# 06-I225-1.net
KiCad netlist of a schematic drawn in Altium Designer
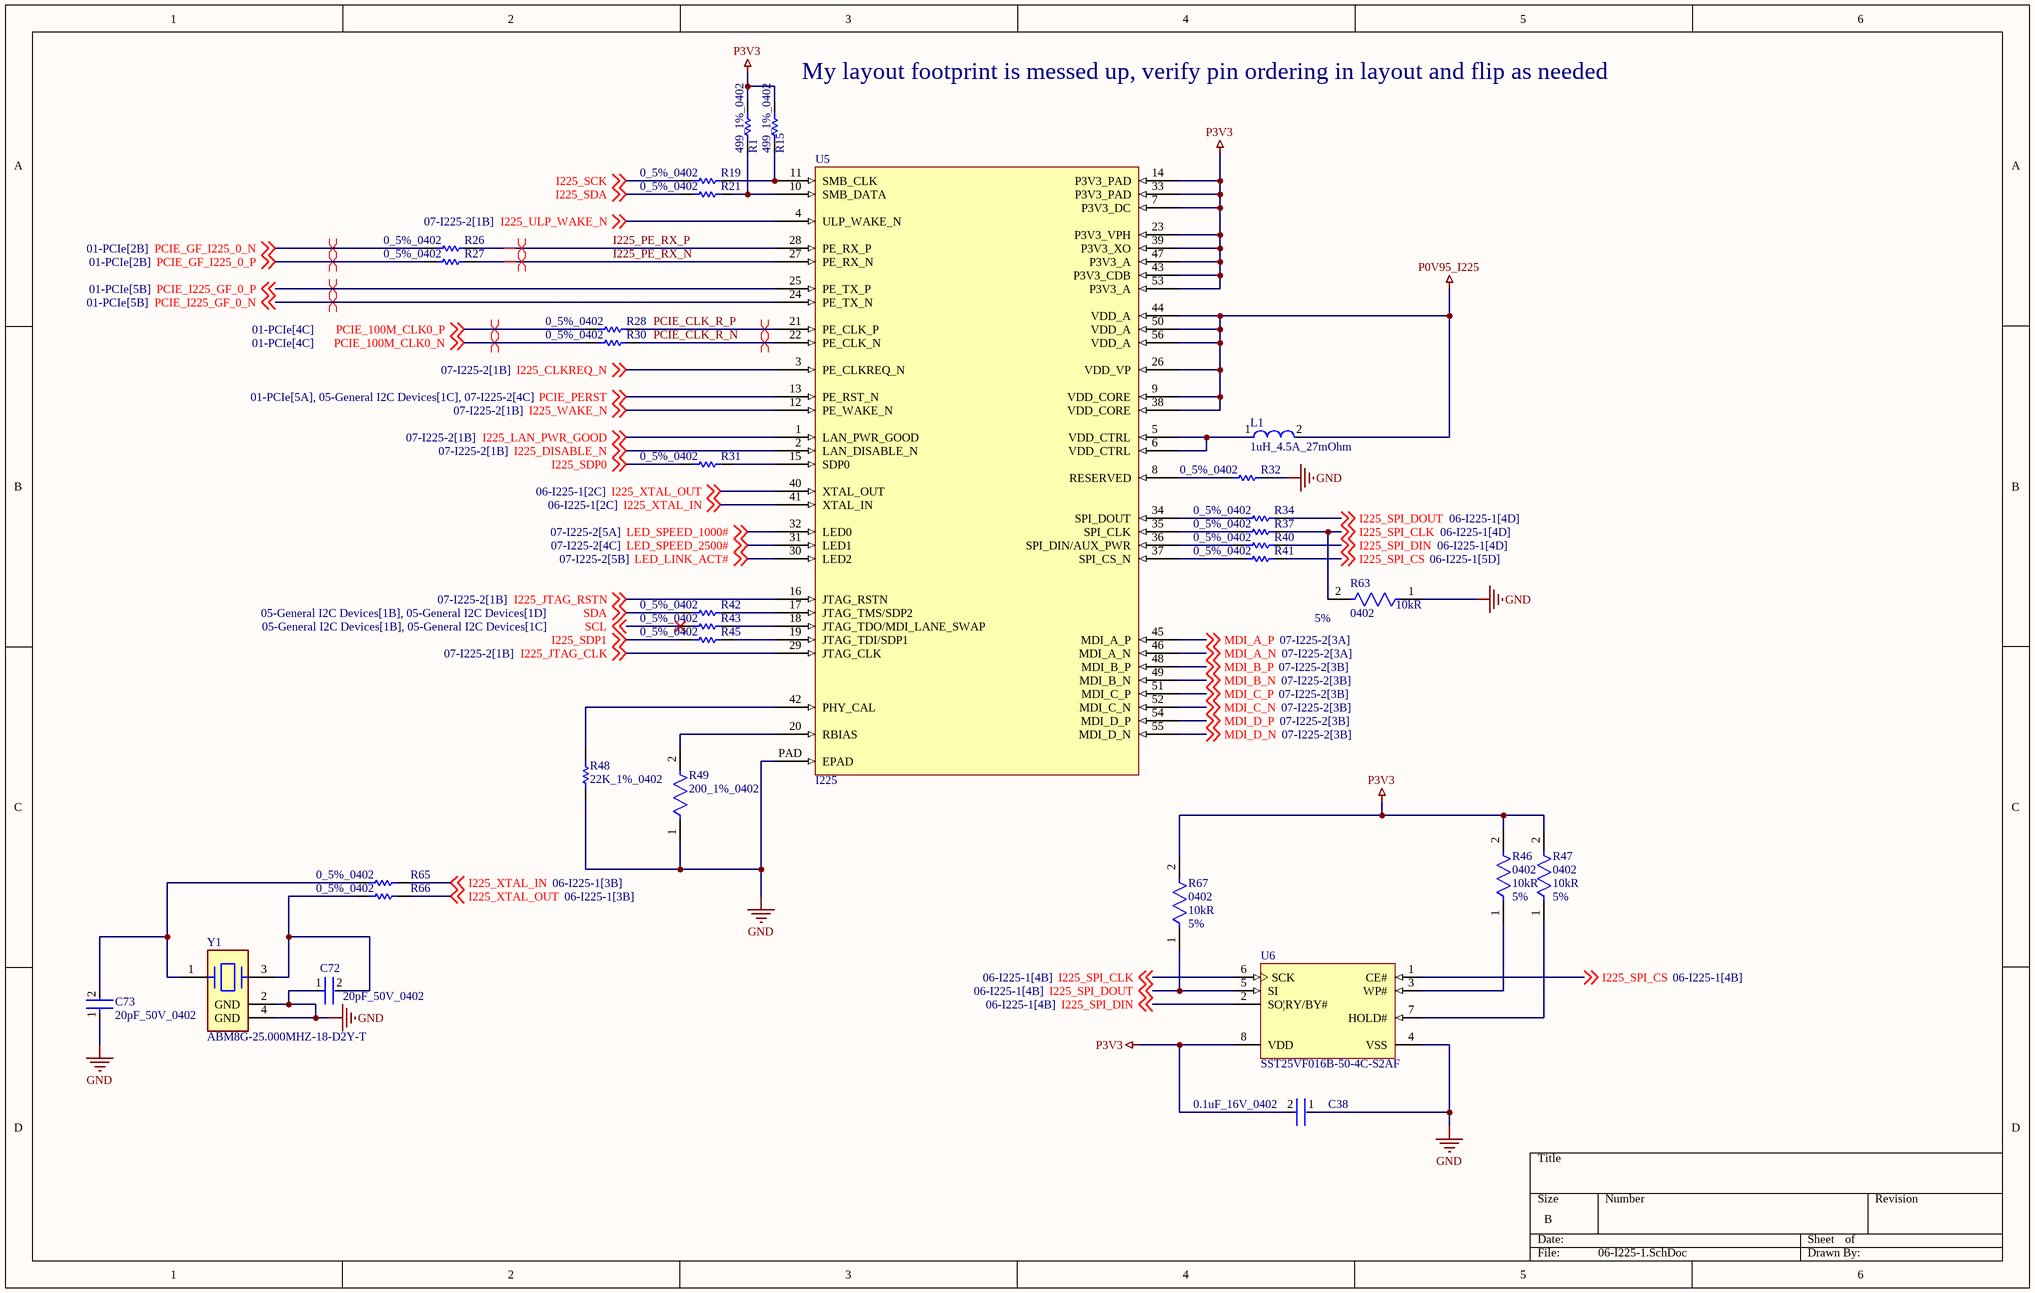
[diagram p0: 06-I225-1.SchDoc]

(export (version "E")
  (design (tool "Eeschema 10.0.6"))
  (components
    (comp (ref "C38")
      (value "0.1uF_16V_0402")
      (footprint "FP-GRM15-MFG")
      (description "CAP CER 0.1UF 16V X7R 0402")
      (fields (field (name "MANUFACTURER PART NUMBER") "GRM155R71C104KA88D") (field (name "TOLERANCE") "10%"))
      (libsource (lib "Altium Content Vault") (part "236180d848d6139a670b325ea6854c9"))
    )
    (comp (ref "C72")
      (value "20pF_50V_0402")
      (footprint "FP-C0402-BB-MFG")
      (description "CAP CER 20PF 50V 5% NP0 0402")
      (fields
        (field (name "MANUFACTURER PART NUMBER") "C0402C200J5GACTU")
        (field (name "OCTOPART") "https://octopart.com/c0402c200j5gactu-kemet-9143900")
      )
      (libsource (lib "Altium Content Vault") (part "b4654b650e69147ec39a6b967a45e02"))
    )
    (comp (ref "C73")
      (value "20pF_50V_0402")
      (footprint "FP-C0402-BB-MFG")
      (description "CAP CER 20PF 50V 5% NP0 0402")
      (fields
        (field (name "MANUFACTURER PART NUMBER") "C0402C200J5GACTU")
        (field (name "OCTOPART") "https://octopart.com/c0402c200j5gactu-kemet-9143900")
      )
      (libsource (lib "Altium Content Vault") (part "b4654b650e69147ec39a6b967a45e02"))
    )
    (comp (ref "L1")
      (value "1uH_4.5A_27mOhm")
      (footprint "FP-IHLP-1616BZ-FP_1_8545x-MFG")
      (description "Fixed Inductors Commercial Low DCR Series SMT 1uH 4.5A 27mΩ 20%")
      (fields (field (name "TOLERANCE") "20%"))
      (libsource (lib "Altium Content Vault") (part "725321dda6339637d4d059423bc1c3c"))
    )
    (comp (ref "R1")
      (value "499_1%_0402")
      (footprint "RESC1005X40X25LL05T05")
      (fields (field (name "MANUFACTURER") "Panasonic") (field (name "PART NUMBER") "ERJ-2RKF4990X"))
      (libsource (lib "Altium Content Vault") (part "RES"))
    )
    (comp (ref "R15")
      (value "499_1%_0402")
      (footprint "RESC1005X40X25LL05T05")
      (fields (field (name "MANUFACTURER") "Panasonic") (field (name "PART NUMBER") "ERJ-2RKF4990X"))
      (libsource (lib "Altium Content Vault") (part "RES"))
    )
    (comp (ref "R19")
      (value "0_5%_0402")
      (footprint "RESC1005X40X25LL10T10")
      (fields (field (name "MANUFACTURER") "KOA Speer") (field (name "PART NUMBER") "RK73Z1ETTP"))
      (libsource (lib "Altium Content Vault") (part "RES"))
    )
    (comp (ref "R21")
      (value "0_5%_0402")
      (footprint "RESC1005X40X25LL10T10")
      (fields (field (name "MANUFACTURER") "KOA Speer") (field (name "PART NUMBER") "RK73Z1ETTP"))
      (libsource (lib "Altium Content Vault") (part "RES"))
    )
    (comp (ref "R26")
      (value "0_5%_0402")
      (footprint "RESC1005X40X25LL10T10")
      (fields (field (name "MANUFACTURER") "KOA Speer") (field (name "PART NUMBER") "RK73Z1ETTP"))
      (libsource (lib "Altium Content Vault") (part "RES"))
    )
    (comp (ref "R27")
      (value "0_5%_0402")
      (footprint "RESC1005X40X25LL10T10")
      (fields (field (name "MANUFACTURER") "KOA Speer") (field (name "PART NUMBER") "RK73Z1ETTP"))
      (libsource (lib "Altium Content Vault") (part "RES"))
    )
    (comp (ref "R28")
      (value "0_5%_0402")
      (footprint "RESC1005X40X25LL10T10")
      (fields (field (name "MANUFACTURER") "KOA Speer") (field (name "PART NUMBER") "RK73Z1ETTP"))
      (libsource (lib "Altium Content Vault") (part "RES"))
    )
    (comp (ref "R30")
      (value "0_5%_0402")
      (footprint "RESC1005X40X25LL10T10")
      (fields (field (name "MANUFACTURER") "KOA Speer") (field (name "PART NUMBER") "RK73Z1ETTP"))
      (libsource (lib "Altium Content Vault") (part "RES"))
    )
    (comp (ref "R31")
      (value "0_5%_0402")
      (footprint "RESC1005X40X25LL10T10")
      (fields (field (name "MANUFACTURER") "KOA Speer") (field (name "PART NUMBER") "RK73Z1ETTP"))
      (libsource (lib "Altium Content Vault") (part "RES"))
    )
    (comp (ref "R32")
      (value "0_5%_0402")
      (footprint "RESC1005X40X25LL10T10")
      (fields (field (name "MANUFACTURER") "KOA Speer") (field (name "PART NUMBER") "RK73Z1ETTP"))
      (libsource (lib "Altium Content Vault") (part "RES"))
    )
    (comp (ref "R34")
      (value "0_5%_0402")
      (footprint "RESC1005X40X25LL10T10")
      (fields (field (name "MANUFACTURER") "KOA Speer") (field (name "PART NUMBER") "RK73Z1ETTP"))
      (libsource (lib "Altium Content Vault") (part "RES"))
    )
    (comp (ref "R37")
      (value "0_5%_0402")
      (footprint "RESC1005X40X25LL10T10")
      (fields (field (name "MANUFACTURER") "KOA Speer") (field (name "PART NUMBER") "RK73Z1ETTP"))
      (libsource (lib "Altium Content Vault") (part "RES"))
    )
    (comp (ref "R40")
      (value "0_5%_0402")
      (footprint "RESC1005X40X25LL10T10")
      (fields (field (name "MANUFACTURER") "KOA Speer") (field (name "PART NUMBER") "RK73Z1ETTP"))
      (libsource (lib "Altium Content Vault") (part "RES"))
    )
    (comp (ref "R41")
      (value "0_5%_0402")
      (footprint "RESC1005X40X25LL10T10")
      (fields (field (name "MANUFACTURER") "KOA Speer") (field (name "PART NUMBER") "RK73Z1ETTP"))
      (libsource (lib "Altium Content Vault") (part "RES"))
    )
    (comp (ref "R42")
      (value "0_5%_0402")
      (footprint "RESC1005X40X25LL10T10")
      (fields (field (name "MANUFACTURER") "KOA Speer") (field (name "PART NUMBER") "RK73Z1ETTP"))
      (libsource (lib "Altium Content Vault") (part "RES"))
    )
    (comp (ref "R43")
      (value "0_5%_0402")
      (footprint "RESC1005X40X25LL10T10")
      (fields (field (name "MANUFACTURER") "KOA Speer") (field (name "PART NUMBER") "RK73Z1ETTP"))
      (libsource (lib "Altium Content Vault") (part "RES"))
    )
    (comp (ref "R45")
      (value "0_5%_0402")
      (footprint "RESC1005X40X25LL10T10")
      (fields (field (name "MANUFACTURER") "KOA Speer") (field (name "PART NUMBER") "RK73Z1ETTP"))
      (libsource (lib "Altium Content Vault") (part "RES"))
    )
    (comp (ref "R46")
      (value "CRCW040210K0JNED")
      (footprint "FP-CRCW0402-e3-IPC_B")
      (description "RES Thick Film, 10kΩ, 5%, 0.063W, 200ppm/°C, 0402")
      (fields
        (field (name "CASE/PACKAGE") "0402")
        (field (name "RESISTANCE") "10kR")
        (field (name "TOLERANCE") "5%")
      )
      (libsource (lib "Altium Content Vault") (part "1029c3af85768c4190bb7ad29bc67b5"))
    )
    (comp (ref "R47")
      (value "CRCW040210K0JNED")
      (footprint "FP-CRCW0402-e3-IPC_B")
      (description "RES Thick Film, 10kΩ, 5%, 0.063W, 200ppm/°C, 0402")
      (fields
        (field (name "CASE/PACKAGE") "0402")
        (field (name "RESISTANCE") "10kR")
        (field (name "TOLERANCE") "5%")
      )
      (libsource (lib "Altium Content Vault") (part "1029c3af85768c4190bb7ad29bc67b5"))
    )
    (comp (ref "R48")
      (value "22K_1%_0402")
      (footprint "RESC1005X40X25NL05T05")
      (fields (field (name "PART NUMBER") "CRCW040222K0FKED") (field (name "MANUFACTURER") "Vishay Dale"))
      (libsource (lib "Altium Content Vault") (part "RES"))
    )
    (comp (ref "R49")
      (value "200_1%_0402")
      (footprint "FP-CRCW0402-e3-IPC_C")
      (description "RES Thick Film, 200Ω, 1%, 0.063W, 100ppm/°C, 0402")
      (fields (field (name "TOLERANCE") "1%"))
      (libsource (lib "Altium Content Vault") (part "1029c3af85768c4190bb7ad29bc67b5"))
    )
    (comp (ref "R63")
      (value "CRCW040210K0JNED")
      (footprint "FP-CRCW0402-e3-IPC_B")
      (description "RES Thick Film, 10kΩ, 5%, 0.063W, 200ppm/°C, 0402")
      (fields
        (field (name "CASE/PACKAGE") "0402")
        (field (name "RESISTANCE") "10kR")
        (field (name "TOLERANCE") "5%")
      )
      (libsource (lib "Altium Content Vault") (part "1029c3af85768c4190bb7ad29bc67b5"))
    )
    (comp (ref "R65")
      (value "0_5%_0402")
      (footprint "RESC1005X40X25LL10T10")
      (fields (field (name "MANUFACTURER") "KOA Speer") (field (name "PART NUMBER") "RK73Z1ETTP"))
      (libsource (lib "Altium Content Vault") (part "RES"))
    )
    (comp (ref "R66")
      (value "0_5%_0402")
      (footprint "RESC1005X40X25LL10T10")
      (fields (field (name "MANUFACTURER") "KOA Speer") (field (name "PART NUMBER") "RK73Z1ETTP"))
      (libsource (lib "Altium Content Vault") (part "RES"))
    )
    (comp (ref "R67")
      (value "CRCW040210K0JNED")
      (footprint "FP-CRCW0402-e3-IPC_B")
      (description "RES Thick Film, 10kΩ, 5%, 0.063W, 200ppm/°C, 0402")
      (fields
        (field (name "CASE/PACKAGE") "0402")
        (field (name "RESISTANCE") "10kR")
        (field (name "TOLERANCE") "5%")
      )
      (libsource (lib "Altium Content Vault") (part "1029c3af85768c4190bb7ad29bc67b5"))
    )
    (comp (ref "U5") (value "I225") (footprint "I225 QFN56") (libsource (lib "TimeStick_Lib") (part "I225")))
    (comp (ref "U6")
      (value "SST25VF016B-50-4C-S2AF")
      (footprint "MCHP-SOIC-S2A8_M")
      (description "16 Mbit SPI Serial Flash, 2.7 to 3.6 V, 50 MHz, 0 to 70 degC, 8-pin SOIC (S2A8), Tube")
      (fields (field (name "MANUFACTURER") "Microchip"))
      (libsource (lib "Altium Content Vault") (part "MCHP-SST25VFXXXB-SOIX-8"))
    )
    (comp (ref "Y1")
      (value "ABM8G-25.000MHZ-18-D2Y-T")
      (footprint "FP-ABM8G-MFG")
      (description "CRYSTAL 25.0000MHZ 18PF SMD")
      (fields
        (field (name "MANUFACTURER") "Abracon")
        (field (name "OCTOPART") "https://octopart.com/abm8g-25.000mhz-18-d2y-t-abracon-12676602")
      )
      (libsource (lib "Altium Content Vault") (part "82af6c543cb7a88a4cbd02a3a01c293"))
    )
  )
  (nets
    (net (code "1") (name "/I225_PE_RX_N") (class "Default")
      (node (ref "R27") (pin "2") (pinfunction "2_2") (pintype "passive"))
      (node (ref "U5") (pin "27") (pinfunction "PE_RX_N_27") (pintype "input"))
    )
    (net (code "2") (name "/I225_PE_RX_P") (class "Default")
      (node (ref "R26") (pin "2") (pinfunction "2_2") (pintype "passive"))
      (node (ref "U5") (pin "28") (pinfunction "PE_RX_P_28") (pintype "input"))
    )
    (net (code "3") (name "/PCIE_CLK_R_N") (class "Default")
      (node (ref "R30") (pin "2") (pinfunction "2_2") (pintype "passive"))
      (node (ref "U5") (pin "22") (pinfunction "PE_CLK_N_22") (pintype "input"))
    )
    (net (code "4") (name "/PCIE_CLK_R_P") (class "Default")
      (node (ref "R28") (pin "2") (pinfunction "2_2") (pintype "passive"))
      (node (ref "U5") (pin "21") (pinfunction "PE_CLK_P_21") (pintype "input"))
    )
    (net (code "5") (name "GND") (class "Default")
      (node (ref "C38") (pin "1") (pinfunction "1_1") (pintype "passive"))
      (node (ref "C72") (pin "1") (pinfunction "1_1") (pintype "passive"))
      (node (ref "C73") (pin "1") (pinfunction "1_1") (pintype "passive"))
      (node (ref "R32") (pin "2") (pinfunction "2_2") (pintype "passive"))
      (node (ref "R48") (pin "1") (pinfunction "1_1") (pintype "passive"))
      (node (ref "R49") (pin "1") (pinfunction "1_1") (pintype "passive"))
      (node (ref "R63") (pin "1") (pinfunction "1_1") (pintype "passive"))
      (node (ref "U5") (pin "PAD") (pinfunction "EPAD_PAD") (pintype "input"))
      (node (ref "U6") (pin "4") (pinfunction "VSS_4") (pintype "power_in"))
      (node (ref "Y1") (pin "2") (pinfunction "GND_2") (pintype "power_in"))
      (node (ref "Y1") (pin "4") (pinfunction "GND_4") (pintype "power_in"))
    )
    (net (code "6") (name "I225_CLKREQ_N") (class "Default")
      (node (ref "U5") (pin "3") (pinfunction "PE_CLKREQ_N_3") (pintype "input"))
    )
    (net (code "7") (name "I225_DISABLE_N") (class "Default")
      (node (ref "U5") (pin "2") (pinfunction "LAN_DISABLE_N_2") (pintype "input"))
    )
    (net (code "8") (name "I225_JTAG_CLK") (class "Default")
      (node (ref "U5") (pin "29") (pinfunction "JTAG_CLK_29") (pintype "input"))
    )
    (net (code "9") (name "I225_JTAG_RSTN") (class "Default")
      (node (ref "U5") (pin "16") (pinfunction "JTAG_RSTN_16") (pintype "input"))
    )
    (net (code "10") (name "I225_LAN_PWR_GOOD") (class "Default")
      (node (ref "U5") (pin "1") (pinfunction "LAN_PWR_GOOD_1") (pintype "input"))
    )
    (net (code "11") (name "I225_SCK") (class "Default")
      (node (ref "R19") (pin "1") (pinfunction "1_1") (pintype "passive"))
    )
    (net (code "12") (name "I225_SDA") (class "Default")
      (node (ref "R21") (pin "1") (pinfunction "1_1") (pintype "passive"))
    )
    (net (code "13") (name "I225_SDP0") (class "Default")
      (node (ref "R31") (pin "1") (pinfunction "1_1") (pintype "passive"))
    )
    (net (code "14") (name "I225_SDP1") (class "Default")
      (node (ref "R45") (pin "1") (pinfunction "1_1") (pintype "passive"))
    )
    (net (code "15") (name "I225_SPI_CLK") (class "Default")
      (node (ref "R37") (pin "2") (pinfunction "2_2") (pintype "passive"))
      (node (ref "R63") (pin "2") (pinfunction "2_2") (pintype "passive"))
      (node (ref "U6") (pin "6") (pinfunction "SCK_6") (pintype "input"))
    )
    (net (code "16") (name "I225_SPI_CS") (class "Default")
      (node (ref "R41") (pin "2") (pinfunction "2_2") (pintype "passive"))
      (node (ref "U6") (pin "1") (pinfunction "CE#_1") (pintype "input"))
    )
    (net (code "17") (name "I225_SPI_DIN") (class "Default")
      (node (ref "R40") (pin "2") (pinfunction "2_2") (pintype "passive"))
      (node (ref "U6") (pin "2") (pinfunction "SO¦RY/BY#_2") (pintype "tri_state"))
    )
    (net (code "18") (name "I225_SPI_DOUT") (class "Default")
      (node (ref "R34") (pin "2") (pinfunction "2_2") (pintype "passive"))
      (node (ref "R67") (pin "1") (pinfunction "1_1") (pintype "passive"))
      (node (ref "U6") (pin "5") (pinfunction "SI_5") (pintype "input"))
    )
    (net (code "19") (name "I225_ULP_WAKE_N") (class "Default")
      (node (ref "U5") (pin "4") (pinfunction "ULP_WAKE_N_4") (pintype "input"))
    )
    (net (code "20") (name "I225_WAKE_N") (class "Default")
      (node (ref "U5") (pin "12") (pinfunction "PE_WAKE_N_12") (pintype "input"))
    )
    (net (code "21") (name "I225_XTAL_IN") (class "Default")
      (node (ref "R65") (pin "2") (pinfunction "2_2") (pintype "passive"))
      (node (ref "U5") (pin "41") (pinfunction "XTAL_IN_41") (pintype "input"))
    )
    (net (code "22") (name "I225_XTAL_OUT") (class "Default")
      (node (ref "R66") (pin "2") (pinfunction "2_2") (pintype "passive"))
      (node (ref "U5") (pin "40") (pinfunction "XTAL_OUT_40") (pintype "input"))
    )
    (net (code "23") (name "LED_LINK_ACT#") (class "Default")
      (node (ref "U5") (pin "30") (pinfunction "LED2_30") (pintype "input"))
    )
    (net (code "24") (name "LED_SPEED_1000#") (class "Default")
      (node (ref "U5") (pin "32") (pinfunction "LED0_32") (pintype "input"))
    )
    (net (code "25") (name "LED_SPEED_2500#") (class "Default")
      (node (ref "U5") (pin "31") (pinfunction "LED1_31") (pintype "input"))
    )
    (net (code "26") (name "MDI_A_N") (class "Default")
      (node (ref "U5") (pin "46") (pinfunction "MDI_A_N_46") (pintype "input"))
    )
    (net (code "27") (name "MDI_A_P") (class "Default")
      (node (ref "U5") (pin "45") (pinfunction "MDI_A_P_45") (pintype "input"))
    )
    (net (code "28") (name "MDI_B_N") (class "Default")
      (node (ref "U5") (pin "49") (pinfunction "MDI_B_N_49") (pintype "input"))
    )
    (net (code "29") (name "MDI_B_P") (class "Default")
      (node (ref "U5") (pin "48") (pinfunction "MDI_B_P_48") (pintype "input"))
    )
    (net (code "30") (name "MDI_C_N") (class "Default")
      (node (ref "U5") (pin "52") (pinfunction "MDI_C_N_52") (pintype "input"))
    )
    (net (code "31") (name "MDI_C_P") (class "Default")
      (node (ref "U5") (pin "51") (pinfunction "MDI_C_P_51") (pintype "input"))
    )
    (net (code "32") (name "MDI_D_N") (class "Default")
      (node (ref "U5") (pin "55") (pinfunction "MDI_D_N_55") (pintype "input"))
    )
    (net (code "33") (name "MDI_D_P") (class "Default")
      (node (ref "U5") (pin "54") (pinfunction "MDI_D_P_54") (pintype "input"))
    )
    (net (code "34") (name "Net-(C72-Pad2)") (class "Default")
      (node (ref "C72") (pin "2") (pinfunction "2_2") (pintype "passive"))
      (node (ref "R66") (pin "1") (pinfunction "1_1") (pintype "passive"))
      (node (ref "Y1") (pin "3") (pinfunction "3_3") (pintype "passive"))
    )
    (net (code "35") (name "Net-(C73-Pad2)") (class "Default")
      (node (ref "C73") (pin "2") (pinfunction "2_2") (pintype "passive"))
      (node (ref "R65") (pin "1") (pinfunction "1_1") (pintype "passive"))
      (node (ref "Y1") (pin "1") (pinfunction "1_1") (pintype "passive"))
    )
    (net (code "36") (name "Net-(L1-Pad1)") (class "Default")
      (node (ref "L1") (pin "1") (pinfunction "1_1") (pintype "passive"))
      (node (ref "U5") (pin "5") (pinfunction "VDD_CTRL_5") (pintype "input"))
      (node (ref "U5") (pin "6") (pinfunction "VDD_CTRL_6") (pintype "input"))
    )
    (net (code "37") (name "Net-(U5-JTAG_TDI{slash}SDP1)") (class "Default")
      (node (ref "R45") (pin "2") (pinfunction "2_2") (pintype "passive"))
      (node (ref "U5") (pin "19") (pinfunction "JTAG_TDI/SDP1_19") (pintype "input"))
    )
    (net (code "38") (name "Net-(U5-JTAG_TDO{slash}MDI_LANE_SWAP)") (class "Default")
      (node (ref "R43") (pin "2") (pinfunction "2_2") (pintype "passive"))
      (node (ref "U5") (pin "18") (pinfunction "JTAG_TDO/MDI_LANE_SWAP_18") (pintype "input"))
    )
    (net (code "39") (name "Net-(U5-JTAG_TMS{slash}SDP2)") (class "Default")
      (node (ref "R42") (pin "2") (pinfunction "2_2") (pintype "passive"))
      (node (ref "U5") (pin "17") (pinfunction "JTAG_TMS/SDP2_17") (pintype "input"))
    )
    (net (code "40") (name "Net-(U5-PHY_CAL)") (class "Default")
      (node (ref "R48") (pin "2") (pinfunction "2_2") (pintype "passive"))
      (node (ref "U5") (pin "42") (pinfunction "PHY_CAL_42") (pintype "input"))
    )
    (net (code "41") (name "Net-(U5-RBIAS)") (class "Default")
      (node (ref "R49") (pin "2") (pinfunction "2_2") (pintype "passive"))
      (node (ref "U5") (pin "20") (pinfunction "RBIAS_20") (pintype "input"))
    )
    (net (code "42") (name "Net-(U5-RESERVED)") (class "Default")
      (node (ref "R32") (pin "1") (pinfunction "1_1") (pintype "passive"))
      (node (ref "U5") (pin "8") (pinfunction "RESERVED_8") (pintype "input"))
    )
    (net (code "43") (name "Net-(U5-SDP0)") (class "Default")
      (node (ref "R31") (pin "2") (pinfunction "2_2") (pintype "passive"))
      (node (ref "U5") (pin "15") (pinfunction "SDP0_15") (pintype "input"))
    )
    (net (code "44") (name "Net-(U5-SMB_CLK)") (class "Default")
      (node (ref "R15") (pin "1") (pinfunction "1_1") (pintype "passive"))
      (node (ref "R19") (pin "2") (pinfunction "2_2") (pintype "passive"))
      (node (ref "U5") (pin "11") (pinfunction "SMB_CLK_11") (pintype "input"))
    )
    (net (code "45") (name "Net-(U5-SMB_DATA)") (class "Default")
      (node (ref "R1") (pin "1") (pinfunction "1_1") (pintype "passive"))
      (node (ref "R21") (pin "2") (pinfunction "2_2") (pintype "passive"))
      (node (ref "U5") (pin "10") (pinfunction "SMB_DATA_10") (pintype "input"))
    )
    (net (code "46") (name "Net-(U5-SPI_CLK)") (class "Default")
      (node (ref "R37") (pin "1") (pinfunction "1_1") (pintype "passive"))
      (node (ref "U5") (pin "35") (pinfunction "SPI_CLK_35") (pintype "input"))
    )
    (net (code "47") (name "Net-(U5-SPI_CS_N)") (class "Default")
      (node (ref "R41") (pin "1") (pinfunction "1_1") (pintype "passive"))
      (node (ref "U5") (pin "37") (pinfunction "SPI_CS_N_37") (pintype "input"))
    )
    (net (code "48") (name "Net-(U5-SPI_DIN{slash}AUX_PWR)") (class "Default")
      (node (ref "R40") (pin "1") (pinfunction "1_1") (pintype "passive"))
      (node (ref "U5") (pin "36") (pinfunction "SPI_DIN/AUX_PWR_36") (pintype "input"))
    )
    (net (code "49") (name "Net-(U5-SPI_DOUT)") (class "Default")
      (node (ref "R34") (pin "1") (pinfunction "1_1") (pintype "passive"))
      (node (ref "U5") (pin "34") (pinfunction "SPI_DOUT_34") (pintype "input"))
    )
    (net (code "50") (name "Net-(U6-HOLD#)") (class "Default")
      (node (ref "R47") (pin "1") (pinfunction "1_1") (pintype "passive"))
      (node (ref "U6") (pin "7") (pinfunction "HOLD#_7") (pintype "input"))
    )
    (net (code "51") (name "Net-(U6-WP#)") (class "Default")
      (node (ref "R46") (pin "1") (pinfunction "1_1") (pintype "passive"))
      (node (ref "U6") (pin "3") (pinfunction "WP#_3") (pintype "input"))
    )
    (net (code "52") (name "P0V95_I225") (class "Default")
      (node (ref "L1") (pin "2") (pinfunction "2_2") (pintype "passive"))
      (node (ref "U5") (pin "26") (pinfunction "VDD_VP_26") (pintype "input"))
      (node (ref "U5") (pin "38") (pinfunction "VDD_CORE_38") (pintype "input"))
      (node (ref "U5") (pin "44") (pinfunction "VDD_A_44") (pintype "input"))
      (node (ref "U5") (pin "50") (pinfunction "VDD_A_50") (pintype "input"))
      (node (ref "U5") (pin "56") (pinfunction "VDD_A_56") (pintype "input"))
      (node (ref "U5") (pin "9") (pinfunction "VDD_CORE_9") (pintype "input"))
    )
    (net (code "53") (name "P3V3") (class "Default")
      (node (ref "C38") (pin "2") (pinfunction "2_2") (pintype "passive"))
      (node (ref "R1") (pin "2") (pinfunction "2_2") (pintype "passive"))
      (node (ref "R15") (pin "2") (pinfunction "2_2") (pintype "passive"))
      (node (ref "R46") (pin "2") (pinfunction "2_2") (pintype "passive"))
      (node (ref "R47") (pin "2") (pinfunction "2_2") (pintype "passive"))
      (node (ref "R67") (pin "2") (pinfunction "2_2") (pintype "passive"))
      (node (ref "U5") (pin "14") (pinfunction "P3V3_PAD_14") (pintype "input"))
      (node (ref "U5") (pin "23") (pinfunction "P3V3_VPH_23") (pintype "input"))
      (node (ref "U5") (pin "33") (pinfunction "P3V3_PAD_33") (pintype "input"))
      (node (ref "U5") (pin "39") (pinfunction "P3V3_XO_39") (pintype "input"))
      (node (ref "U5") (pin "43") (pinfunction "P3V3_CDB_43") (pintype "input"))
      (node (ref "U5") (pin "47") (pinfunction "P3V3_A_47") (pintype "input"))
      (node (ref "U5") (pin "53") (pinfunction "P3V3_A_53") (pintype "input"))
      (node (ref "U5") (pin "7") (pinfunction "P3V3_DC_7") (pintype "input"))
      (node (ref "U6") (pin "8") (pinfunction "VDD_8") (pintype "power_in"))
    )
    (net (code "54") (name "PCIE_100M_CLK0_N") (class "Default")
      (node (ref "R30") (pin "1") (pinfunction "1_1") (pintype "passive"))
    )
    (net (code "55") (name "PCIE_100M_CLK0_P") (class "Default")
      (node (ref "R28") (pin "1") (pinfunction "1_1") (pintype "passive"))
    )
    (net (code "56") (name "PCIE_GF_I225_0_N") (class "Default")
      (node (ref "R26") (pin "1") (pinfunction "1_1") (pintype "passive"))
    )
    (net (code "57") (name "PCIE_GF_I225_0_P") (class "Default")
      (node (ref "R27") (pin "1") (pinfunction "1_1") (pintype "passive"))
    )
    (net (code "58") (name "PCIE_I225_GF_0_N") (class "Default")
      (node (ref "U5") (pin "24") (pinfunction "PE_TX_N_24") (pintype "input"))
    )
    (net (code "59") (name "PCIE_I225_GF_0_P") (class "Default")
      (node (ref "U5") (pin "25") (pinfunction "PE_TX_P_25") (pintype "input"))
    )
    (net (code "60") (name "PCIE_PERST") (class "Default")
      (node (ref "U5") (pin "13") (pinfunction "PE_RST_N_13") (pintype "input"))
    )
    (net (code "61") (name "SCL") (class "Default")
      (node (ref "R43") (pin "1") (pinfunction "1_1") (pintype "passive"))
    )
    (net (code "62") (name "SDA") (class "Default")
      (node (ref "R42") (pin "1") (pinfunction "1_1") (pintype "passive"))
    )
  )
)
